# WS2812_MATRIX_3.net
KiCad netlist of a schematic drawn in Altium Designer
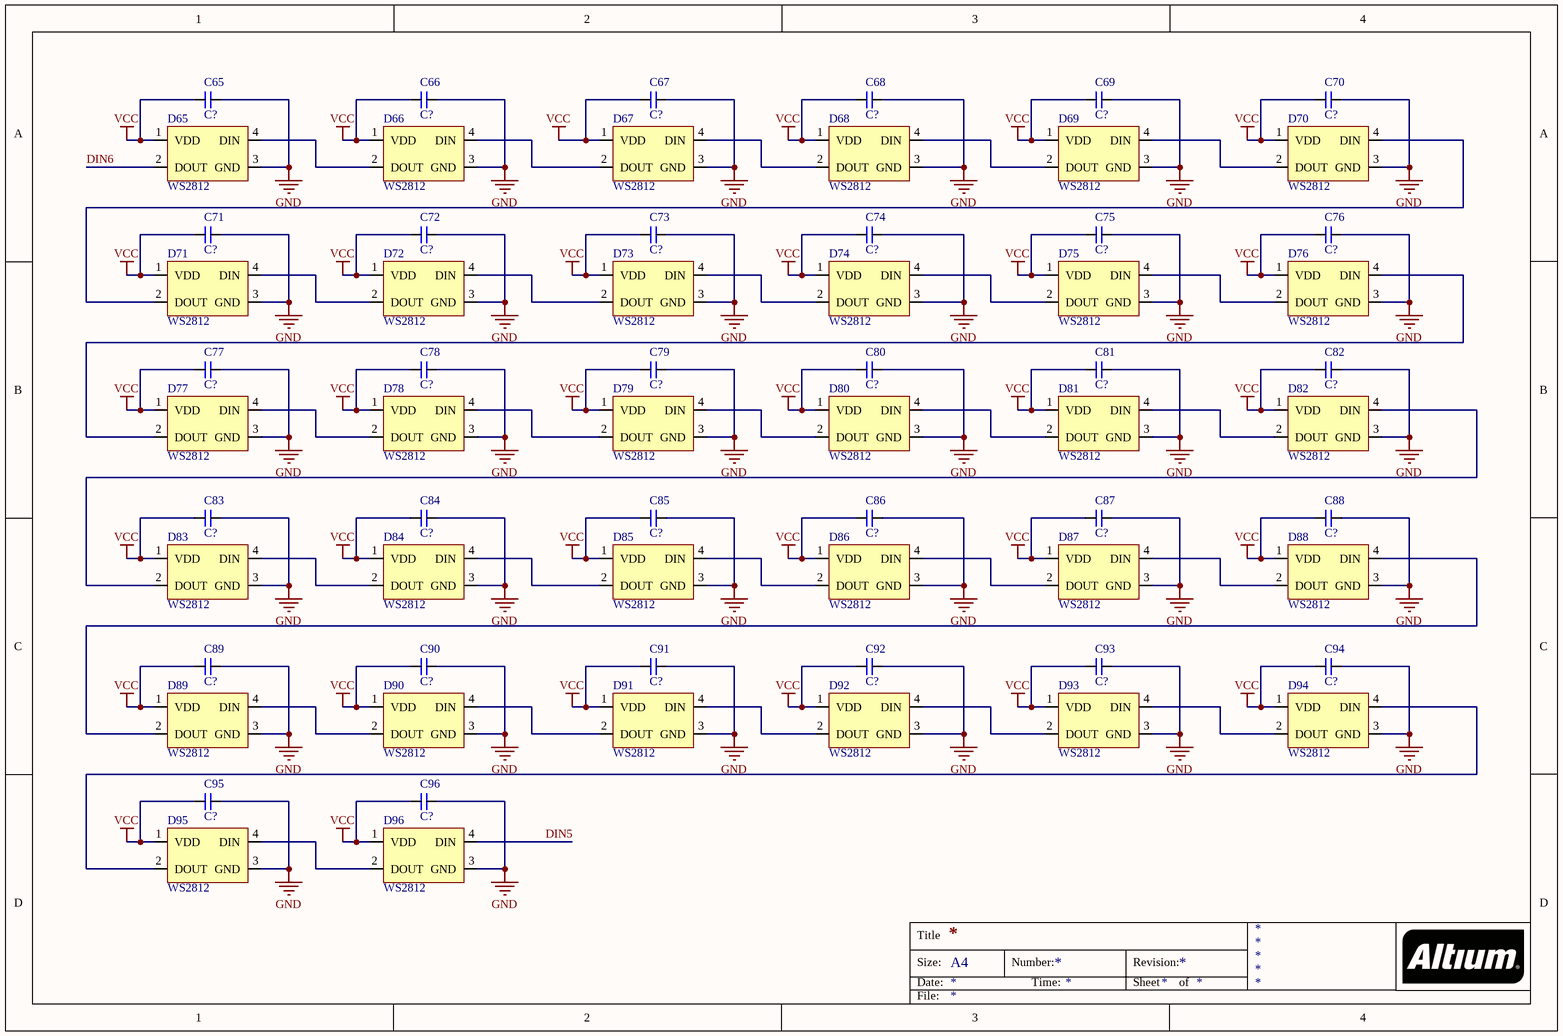
[diagram p0: WS2812_MATRIX_3.SchDoc]

(export (version "E")
  (design (tool "Eeschema 10.0.6"))
  (components
    (comp (ref "C65")
      (value "C?")
      (footprint "C0603")
      (description "Cap")
      (libsource (lib "SCH_Bacsic") (part "CAP"))
    )
    (comp (ref "C66")
      (value "C?")
      (footprint "C0603")
      (description "Cap")
      (libsource (lib "SCH_Bacsic") (part "CAP"))
    )
    (comp (ref "C67")
      (value "C?")
      (footprint "C0603")
      (description "Cap")
      (libsource (lib "SCH_Bacsic") (part "CAP"))
    )
    (comp (ref "C68")
      (value "C?")
      (footprint "C0603")
      (description "Cap")
      (libsource (lib "SCH_Bacsic") (part "CAP"))
    )
    (comp (ref "C69")
      (value "C?")
      (footprint "C0603")
      (description "Cap")
      (libsource (lib "SCH_Bacsic") (part "CAP"))
    )
    (comp (ref "C70")
      (value "C?")
      (footprint "C0603")
      (description "Cap")
      (libsource (lib "SCH_Bacsic") (part "CAP"))
    )
    (comp (ref "C71")
      (value "C?")
      (footprint "C0603")
      (description "Cap")
      (libsource (lib "SCH_Bacsic") (part "CAP"))
    )
    (comp (ref "C72")
      (value "C?")
      (footprint "C0603")
      (description "Cap")
      (libsource (lib "SCH_Bacsic") (part "CAP"))
    )
    (comp (ref "C73")
      (value "C?")
      (footprint "C0603")
      (description "Cap")
      (libsource (lib "SCH_Bacsic") (part "CAP"))
    )
    (comp (ref "C74")
      (value "C?")
      (footprint "C0603")
      (description "Cap")
      (libsource (lib "SCH_Bacsic") (part "CAP"))
    )
    (comp (ref "C75")
      (value "C?")
      (footprint "C0603")
      (description "Cap")
      (libsource (lib "SCH_Bacsic") (part "CAP"))
    )
    (comp (ref "C76")
      (value "C?")
      (footprint "C0603")
      (description "Cap")
      (libsource (lib "SCH_Bacsic") (part "CAP"))
    )
    (comp (ref "C77")
      (value "C?")
      (footprint "C0603")
      (description "Cap")
      (libsource (lib "SCH_Bacsic") (part "CAP"))
    )
    (comp (ref "C78")
      (value "C?")
      (footprint "C0603")
      (description "Cap")
      (libsource (lib "SCH_Bacsic") (part "CAP"))
    )
    (comp (ref "C79")
      (value "C?")
      (footprint "C0603")
      (description "Cap")
      (libsource (lib "SCH_Bacsic") (part "CAP"))
    )
    (comp (ref "C80")
      (value "C?")
      (footprint "C0603")
      (description "Cap")
      (libsource (lib "SCH_Bacsic") (part "CAP"))
    )
    (comp (ref "C81")
      (value "C?")
      (footprint "C0603")
      (description "Cap")
      (libsource (lib "SCH_Bacsic") (part "CAP"))
    )
    (comp (ref "C82")
      (value "C?")
      (footprint "C0603")
      (description "Cap")
      (libsource (lib "SCH_Bacsic") (part "CAP"))
    )
    (comp (ref "C83")
      (value "C?")
      (footprint "C0603")
      (description "Cap")
      (libsource (lib "SCH_Bacsic") (part "CAP"))
    )
    (comp (ref "C84")
      (value "C?")
      (footprint "C0603")
      (description "Cap")
      (libsource (lib "SCH_Bacsic") (part "CAP"))
    )
    (comp (ref "C85")
      (value "C?")
      (footprint "C0603")
      (description "Cap")
      (libsource (lib "SCH_Bacsic") (part "CAP"))
    )
    (comp (ref "C86")
      (value "C?")
      (footprint "C0603")
      (description "Cap")
      (libsource (lib "SCH_Bacsic") (part "CAP"))
    )
    (comp (ref "C87")
      (value "C?")
      (footprint "C0603")
      (description "Cap")
      (libsource (lib "SCH_Bacsic") (part "CAP"))
    )
    (comp (ref "C88")
      (value "C?")
      (footprint "C0603")
      (description "Cap")
      (libsource (lib "SCH_Bacsic") (part "CAP"))
    )
    (comp (ref "C89")
      (value "C?")
      (footprint "C0603")
      (description "Cap")
      (libsource (lib "SCH_Bacsic") (part "CAP"))
    )
    (comp (ref "C90")
      (value "C?")
      (footprint "C0603")
      (description "Cap")
      (libsource (lib "SCH_Bacsic") (part "CAP"))
    )
    (comp (ref "C91")
      (value "C?")
      (footprint "C0603")
      (description "Cap")
      (libsource (lib "SCH_Bacsic") (part "CAP"))
    )
    (comp (ref "C92")
      (value "C?")
      (footprint "C0603")
      (description "Cap")
      (libsource (lib "SCH_Bacsic") (part "CAP"))
    )
    (comp (ref "C93")
      (value "C?")
      (footprint "C0603")
      (description "Cap")
      (libsource (lib "SCH_Bacsic") (part "CAP"))
    )
    (comp (ref "C94")
      (value "C?")
      (footprint "C0603")
      (description "Cap")
      (libsource (lib "SCH_Bacsic") (part "CAP"))
    )
    (comp (ref "C95")
      (value "C?")
      (footprint "C0603")
      (description "Cap")
      (libsource (lib "SCH_Bacsic") (part "CAP"))
    )
    (comp (ref "C96")
      (value "C?")
      (footprint "C0603")
      (description "Cap")
      (libsource (lib "SCH_Bacsic") (part "CAP"))
    )
    (comp (ref "D65")
      (value "WS2812")
      (footprint "WS2812_3528")
      (libsource (lib "SCH_Bacsic") (part "WS2812"))
    )
    (comp (ref "D66")
      (value "WS2812")
      (footprint "WS2812_3528")
      (libsource (lib "SCH_Bacsic") (part "WS2812"))
    )
    (comp (ref "D67")
      (value "WS2812")
      (footprint "WS2812_3528")
      (libsource (lib "SCH_Bacsic") (part "WS2812"))
    )
    (comp (ref "D68")
      (value "WS2812")
      (footprint "WS2812_3528")
      (libsource (lib "SCH_Bacsic") (part "WS2812"))
    )
    (comp (ref "D69")
      (value "WS2812")
      (footprint "WS2812_3528")
      (libsource (lib "SCH_Bacsic") (part "WS2812"))
    )
    (comp (ref "D70")
      (value "WS2812")
      (footprint "WS2812_3528")
      (libsource (lib "SCH_Bacsic") (part "WS2812"))
    )
    (comp (ref "D71")
      (value "WS2812")
      (footprint "WS2812_3528")
      (libsource (lib "SCH_Bacsic") (part "WS2812"))
    )
    (comp (ref "D72")
      (value "WS2812")
      (footprint "WS2812_3528")
      (libsource (lib "SCH_Bacsic") (part "WS2812"))
    )
    (comp (ref "D73")
      (value "WS2812")
      (footprint "WS2812_3528")
      (libsource (lib "SCH_Bacsic") (part "WS2812"))
    )
    (comp (ref "D74")
      (value "WS2812")
      (footprint "WS2812_3528")
      (libsource (lib "SCH_Bacsic") (part "WS2812"))
    )
    (comp (ref "D75")
      (value "WS2812")
      (footprint "WS2812_3528")
      (libsource (lib "SCH_Bacsic") (part "WS2812"))
    )
    (comp (ref "D76")
      (value "WS2812")
      (footprint "WS2812_3528")
      (libsource (lib "SCH_Bacsic") (part "WS2812"))
    )
    (comp (ref "D77")
      (value "WS2812")
      (footprint "WS2812_3528")
      (libsource (lib "SCH_Bacsic") (part "WS2812"))
    )
    (comp (ref "D78")
      (value "WS2812")
      (footprint "WS2812_3528")
      (libsource (lib "SCH_Bacsic") (part "WS2812"))
    )
    (comp (ref "D79")
      (value "WS2812")
      (footprint "WS2812_3528")
      (libsource (lib "SCH_Bacsic") (part "WS2812"))
    )
    (comp (ref "D80")
      (value "WS2812")
      (footprint "WS2812_3528")
      (libsource (lib "SCH_Bacsic") (part "WS2812"))
    )
    (comp (ref "D81")
      (value "WS2812")
      (footprint "WS2812_3528")
      (libsource (lib "SCH_Bacsic") (part "WS2812"))
    )
    (comp (ref "D82")
      (value "WS2812")
      (footprint "WS2812_3528")
      (libsource (lib "SCH_Bacsic") (part "WS2812"))
    )
    (comp (ref "D83")
      (value "WS2812")
      (footprint "WS2812_3528")
      (libsource (lib "SCH_Bacsic") (part "WS2812"))
    )
    (comp (ref "D84")
      (value "WS2812")
      (footprint "WS2812_3528")
      (libsource (lib "SCH_Bacsic") (part "WS2812"))
    )
    (comp (ref "D85")
      (value "WS2812")
      (footprint "WS2812_3528")
      (libsource (lib "SCH_Bacsic") (part "WS2812"))
    )
    (comp (ref "D86")
      (value "WS2812")
      (footprint "WS2812_3528")
      (libsource (lib "SCH_Bacsic") (part "WS2812"))
    )
    (comp (ref "D87")
      (value "WS2812")
      (footprint "WS2812_3528")
      (libsource (lib "SCH_Bacsic") (part "WS2812"))
    )
    (comp (ref "D88")
      (value "WS2812")
      (footprint "WS2812_3528")
      (libsource (lib "SCH_Bacsic") (part "WS2812"))
    )
    (comp (ref "D89")
      (value "WS2812")
      (footprint "WS2812_3528")
      (libsource (lib "SCH_Bacsic") (part "WS2812"))
    )
    (comp (ref "D90")
      (value "WS2812")
      (footprint "WS2812_3528")
      (libsource (lib "SCH_Bacsic") (part "WS2812"))
    )
    (comp (ref "D91")
      (value "WS2812")
      (footprint "WS2812_3528")
      (libsource (lib "SCH_Bacsic") (part "WS2812"))
    )
    (comp (ref "D92")
      (value "WS2812")
      (footprint "WS2812_3528")
      (libsource (lib "SCH_Bacsic") (part "WS2812"))
    )
    (comp (ref "D93")
      (value "WS2812")
      (footprint "WS2812_3528")
      (libsource (lib "SCH_Bacsic") (part "WS2812"))
    )
    (comp (ref "D94")
      (value "WS2812")
      (footprint "WS2812_3528")
      (libsource (lib "SCH_Bacsic") (part "WS2812"))
    )
    (comp (ref "D95")
      (value "WS2812")
      (footprint "WS2812_3528")
      (libsource (lib "SCH_Bacsic") (part "WS2812"))
    )
    (comp (ref "D96")
      (value "WS2812")
      (footprint "WS2812_3528")
      (libsource (lib "SCH_Bacsic") (part "WS2812"))
    )
  )
  (nets
    (net (code "1") (name "/DIN5") (class "Default")
      (node (ref "D96") (pin "4") (pinfunction "DIN_4") (pintype "passive"))
    )
    (net (code "2") (name "/DIN6") (class "Default")
      (node (ref "D65") (pin "2") (pinfunction "DOUT_2") (pintype "passive"))
    )
    (net (code "3") (name "GND") (class "Default")
      (node (ref "C65") (pin "2") (pintype "passive"))
      (node (ref "C66") (pin "2") (pintype "passive"))
      (node (ref "C67") (pin "2") (pintype "passive"))
      (node (ref "C68") (pin "2") (pintype "passive"))
      (node (ref "C69") (pin "2") (pintype "passive"))
      (node (ref "C70") (pin "2") (pintype "passive"))
      (node (ref "C71") (pin "2") (pintype "passive"))
      (node (ref "C72") (pin "2") (pintype "passive"))
      (node (ref "C73") (pin "2") (pintype "passive"))
      (node (ref "C74") (pin "2") (pintype "passive"))
      (node (ref "C75") (pin "2") (pintype "passive"))
      (node (ref "C76") (pin "2") (pintype "passive"))
      (node (ref "C77") (pin "2") (pintype "passive"))
      (node (ref "C78") (pin "2") (pintype "passive"))
      (node (ref "C79") (pin "2") (pintype "passive"))
      (node (ref "C80") (pin "2") (pintype "passive"))
      (node (ref "C81") (pin "2") (pintype "passive"))
      (node (ref "C82") (pin "2") (pintype "passive"))
      (node (ref "C83") (pin "2") (pintype "passive"))
      (node (ref "C84") (pin "2") (pintype "passive"))
      (node (ref "C85") (pin "2") (pintype "passive"))
      (node (ref "C86") (pin "2") (pintype "passive"))
      (node (ref "C87") (pin "2") (pintype "passive"))
      (node (ref "C88") (pin "2") (pintype "passive"))
      (node (ref "C89") (pin "2") (pintype "passive"))
      (node (ref "C90") (pin "2") (pintype "passive"))
      (node (ref "C91") (pin "2") (pintype "passive"))
      (node (ref "C92") (pin "2") (pintype "passive"))
      (node (ref "C93") (pin "2") (pintype "passive"))
      (node (ref "C94") (pin "2") (pintype "passive"))
      (node (ref "C95") (pin "2") (pintype "passive"))
      (node (ref "C96") (pin "2") (pintype "passive"))
      (node (ref "D65") (pin "3") (pinfunction "GND_3") (pintype "passive"))
      (node (ref "D66") (pin "3") (pinfunction "GND_3") (pintype "passive"))
      (node (ref "D67") (pin "3") (pinfunction "GND_3") (pintype "passive"))
      (node (ref "D68") (pin "3") (pinfunction "GND_3") (pintype "passive"))
      (node (ref "D69") (pin "3") (pinfunction "GND_3") (pintype "passive"))
      (node (ref "D70") (pin "3") (pinfunction "GND_3") (pintype "passive"))
      (node (ref "D71") (pin "3") (pinfunction "GND_3") (pintype "passive"))
      (node (ref "D72") (pin "3") (pinfunction "GND_3") (pintype "passive"))
      (node (ref "D73") (pin "3") (pinfunction "GND_3") (pintype "passive"))
      (node (ref "D74") (pin "3") (pinfunction "GND_3") (pintype "passive"))
      (node (ref "D75") (pin "3") (pinfunction "GND_3") (pintype "passive"))
      (node (ref "D76") (pin "3") (pinfunction "GND_3") (pintype "passive"))
      (node (ref "D77") (pin "3") (pinfunction "GND_3") (pintype "passive"))
      (node (ref "D78") (pin "3") (pinfunction "GND_3") (pintype "passive"))
      (node (ref "D79") (pin "3") (pinfunction "GND_3") (pintype "passive"))
      (node (ref "D80") (pin "3") (pinfunction "GND_3") (pintype "passive"))
      (node (ref "D81") (pin "3") (pinfunction "GND_3") (pintype "passive"))
      (node (ref "D82") (pin "3") (pinfunction "GND_3") (pintype "passive"))
      (node (ref "D83") (pin "3") (pinfunction "GND_3") (pintype "passive"))
      (node (ref "D84") (pin "3") (pinfunction "GND_3") (pintype "passive"))
      (node (ref "D85") (pin "3") (pinfunction "GND_3") (pintype "passive"))
      (node (ref "D86") (pin "3") (pinfunction "GND_3") (pintype "passive"))
      (node (ref "D87") (pin "3") (pinfunction "GND_3") (pintype "passive"))
      (node (ref "D88") (pin "3") (pinfunction "GND_3") (pintype "passive"))
      (node (ref "D89") (pin "3") (pinfunction "GND_3") (pintype "passive"))
      (node (ref "D90") (pin "3") (pinfunction "GND_3") (pintype "passive"))
      (node (ref "D91") (pin "3") (pinfunction "GND_3") (pintype "passive"))
      (node (ref "D92") (pin "3") (pinfunction "GND_3") (pintype "passive"))
      (node (ref "D93") (pin "3") (pinfunction "GND_3") (pintype "passive"))
      (node (ref "D94") (pin "3") (pinfunction "GND_3") (pintype "passive"))
      (node (ref "D95") (pin "3") (pinfunction "GND_3") (pintype "passive"))
      (node (ref "D96") (pin "3") (pinfunction "GND_3") (pintype "passive"))
    )
    (net (code "4") (name "Net-(D65-DIN)") (class "Default")
      (node (ref "D65") (pin "4") (pinfunction "DIN_4") (pintype "passive"))
      (node (ref "D66") (pin "2") (pinfunction "DOUT_2") (pintype "passive"))
    )
    (net (code "5") (name "Net-(D66-DIN)") (class "Default")
      (node (ref "D66") (pin "4") (pinfunction "DIN_4") (pintype "passive"))
      (node (ref "D67") (pin "2") (pinfunction "DOUT_2") (pintype "passive"))
    )
    (net (code "6") (name "Net-(D67-DIN)") (class "Default")
      (node (ref "D67") (pin "4") (pinfunction "DIN_4") (pintype "passive"))
      (node (ref "D68") (pin "2") (pinfunction "DOUT_2") (pintype "passive"))
    )
    (net (code "7") (name "Net-(D68-DIN)") (class "Default")
      (node (ref "D68") (pin "4") (pinfunction "DIN_4") (pintype "passive"))
      (node (ref "D69") (pin "2") (pinfunction "DOUT_2") (pintype "passive"))
    )
    (net (code "8") (name "Net-(D69-DIN)") (class "Default")
      (node (ref "D69") (pin "4") (pinfunction "DIN_4") (pintype "passive"))
      (node (ref "D70") (pin "2") (pinfunction "DOUT_2") (pintype "passive"))
    )
    (net (code "9") (name "Net-(D70-DIN)") (class "Default")
      (node (ref "D70") (pin "4") (pinfunction "DIN_4") (pintype "passive"))
      (node (ref "D71") (pin "2") (pinfunction "DOUT_2") (pintype "passive"))
    )
    (net (code "10") (name "Net-(D71-DIN)") (class "Default")
      (node (ref "D71") (pin "4") (pinfunction "DIN_4") (pintype "passive"))
      (node (ref "D72") (pin "2") (pinfunction "DOUT_2") (pintype "passive"))
    )
    (net (code "11") (name "Net-(D72-DIN)") (class "Default")
      (node (ref "D72") (pin "4") (pinfunction "DIN_4") (pintype "passive"))
      (node (ref "D73") (pin "2") (pinfunction "DOUT_2") (pintype "passive"))
    )
    (net (code "12") (name "Net-(D73-DIN)") (class "Default")
      (node (ref "D73") (pin "4") (pinfunction "DIN_4") (pintype "passive"))
      (node (ref "D74") (pin "2") (pinfunction "DOUT_2") (pintype "passive"))
    )
    (net (code "13") (name "Net-(D74-DIN)") (class "Default")
      (node (ref "D74") (pin "4") (pinfunction "DIN_4") (pintype "passive"))
      (node (ref "D75") (pin "2") (pinfunction "DOUT_2") (pintype "passive"))
    )
    (net (code "14") (name "Net-(D75-DIN)") (class "Default")
      (node (ref "D75") (pin "4") (pinfunction "DIN_4") (pintype "passive"))
      (node (ref "D76") (pin "2") (pinfunction "DOUT_2") (pintype "passive"))
    )
    (net (code "15") (name "Net-(D76-DIN)") (class "Default")
      (node (ref "D76") (pin "4") (pinfunction "DIN_4") (pintype "passive"))
      (node (ref "D77") (pin "2") (pinfunction "DOUT_2") (pintype "passive"))
    )
    (net (code "16") (name "Net-(D77-DIN)") (class "Default")
      (node (ref "D77") (pin "4") (pinfunction "DIN_4") (pintype "passive"))
      (node (ref "D78") (pin "2") (pinfunction "DOUT_2") (pintype "passive"))
    )
    (net (code "17") (name "Net-(D78-DIN)") (class "Default")
      (node (ref "D78") (pin "4") (pinfunction "DIN_4") (pintype "passive"))
      (node (ref "D79") (pin "2") (pinfunction "DOUT_2") (pintype "passive"))
    )
    (net (code "18") (name "Net-(D79-DIN)") (class "Default")
      (node (ref "D79") (pin "4") (pinfunction "DIN_4") (pintype "passive"))
      (node (ref "D80") (pin "2") (pinfunction "DOUT_2") (pintype "passive"))
    )
    (net (code "19") (name "Net-(D80-DIN)") (class "Default")
      (node (ref "D80") (pin "4") (pinfunction "DIN_4") (pintype "passive"))
      (node (ref "D81") (pin "2") (pinfunction "DOUT_2") (pintype "passive"))
    )
    (net (code "20") (name "Net-(D81-DIN)") (class "Default")
      (node (ref "D81") (pin "4") (pinfunction "DIN_4") (pintype "passive"))
      (node (ref "D82") (pin "2") (pinfunction "DOUT_2") (pintype "passive"))
    )
    (net (code "21") (name "Net-(D82-DIN)") (class "Default")
      (node (ref "D82") (pin "4") (pinfunction "DIN_4") (pintype "passive"))
      (node (ref "D83") (pin "2") (pinfunction "DOUT_2") (pintype "passive"))
    )
    (net (code "22") (name "Net-(D83-DIN)") (class "Default")
      (node (ref "D83") (pin "4") (pinfunction "DIN_4") (pintype "passive"))
      (node (ref "D84") (pin "2") (pinfunction "DOUT_2") (pintype "passive"))
    )
    (net (code "23") (name "Net-(D84-DIN)") (class "Default")
      (node (ref "D84") (pin "4") (pinfunction "DIN_4") (pintype "passive"))
      (node (ref "D85") (pin "2") (pinfunction "DOUT_2") (pintype "passive"))
    )
    (net (code "24") (name "Net-(D85-DIN)") (class "Default")
      (node (ref "D85") (pin "4") (pinfunction "DIN_4") (pintype "passive"))
      (node (ref "D86") (pin "2") (pinfunction "DOUT_2") (pintype "passive"))
    )
    (net (code "25") (name "Net-(D86-DIN)") (class "Default")
      (node (ref "D86") (pin "4") (pinfunction "DIN_4") (pintype "passive"))
      (node (ref "D87") (pin "2") (pinfunction "DOUT_2") (pintype "passive"))
    )
    (net (code "26") (name "Net-(D87-DIN)") (class "Default")
      (node (ref "D87") (pin "4") (pinfunction "DIN_4") (pintype "passive"))
      (node (ref "D88") (pin "2") (pinfunction "DOUT_2") (pintype "passive"))
    )
    (net (code "27") (name "Net-(D88-DIN)") (class "Default")
      (node (ref "D88") (pin "4") (pinfunction "DIN_4") (pintype "passive"))
      (node (ref "D89") (pin "2") (pinfunction "DOUT_2") (pintype "passive"))
    )
    (net (code "28") (name "Net-(D89-DIN)") (class "Default")
      (node (ref "D89") (pin "4") (pinfunction "DIN_4") (pintype "passive"))
      (node (ref "D90") (pin "2") (pinfunction "DOUT_2") (pintype "passive"))
    )
    (net (code "29") (name "Net-(D90-DIN)") (class "Default")
      (node (ref "D90") (pin "4") (pinfunction "DIN_4") (pintype "passive"))
      (node (ref "D91") (pin "2") (pinfunction "DOUT_2") (pintype "passive"))
    )
    (net (code "30") (name "Net-(D91-DIN)") (class "Default")
      (node (ref "D91") (pin "4") (pinfunction "DIN_4") (pintype "passive"))
      (node (ref "D92") (pin "2") (pinfunction "DOUT_2") (pintype "passive"))
    )
    (net (code "31") (name "Net-(D92-DIN)") (class "Default")
      (node (ref "D92") (pin "4") (pinfunction "DIN_4") (pintype "passive"))
      (node (ref "D93") (pin "2") (pinfunction "DOUT_2") (pintype "passive"))
    )
    (net (code "32") (name "Net-(D93-DIN)") (class "Default")
      (node (ref "D93") (pin "4") (pinfunction "DIN_4") (pintype "passive"))
      (node (ref "D94") (pin "2") (pinfunction "DOUT_2") (pintype "passive"))
    )
    (net (code "33") (name "Net-(D94-DIN)") (class "Default")
      (node (ref "D94") (pin "4") (pinfunction "DIN_4") (pintype "passive"))
      (node (ref "D95") (pin "2") (pinfunction "DOUT_2") (pintype "passive"))
    )
    (net (code "34") (name "Net-(D95-DIN)") (class "Default")
      (node (ref "D95") (pin "4") (pinfunction "DIN_4") (pintype "passive"))
      (node (ref "D96") (pin "2") (pinfunction "DOUT_2") (pintype "passive"))
    )
    (net (code "35") (name "VCC") (class "Default")
      (node (ref "C65") (pin "1") (pintype "passive"))
      (node (ref "C66") (pin "1") (pintype "passive"))
      (node (ref "C67") (pin "1") (pintype "passive"))
      (node (ref "C68") (pin "1") (pintype "passive"))
      (node (ref "C69") (pin "1") (pintype "passive"))
      (node (ref "C70") (pin "1") (pintype "passive"))
      (node (ref "C71") (pin "1") (pintype "passive"))
      (node (ref "C72") (pin "1") (pintype "passive"))
      (node (ref "C73") (pin "1") (pintype "passive"))
      (node (ref "C74") (pin "1") (pintype "passive"))
      (node (ref "C75") (pin "1") (pintype "passive"))
      (node (ref "C76") (pin "1") (pintype "passive"))
      (node (ref "C77") (pin "1") (pintype "passive"))
      (node (ref "C78") (pin "1") (pintype "passive"))
      (node (ref "C79") (pin "1") (pintype "passive"))
      (node (ref "C80") (pin "1") (pintype "passive"))
      (node (ref "C81") (pin "1") (pintype "passive"))
      (node (ref "C82") (pin "1") (pintype "passive"))
      (node (ref "C83") (pin "1") (pintype "passive"))
      (node (ref "C84") (pin "1") (pintype "passive"))
      (node (ref "C85") (pin "1") (pintype "passive"))
      (node (ref "C86") (pin "1") (pintype "passive"))
      (node (ref "C87") (pin "1") (pintype "passive"))
      (node (ref "C88") (pin "1") (pintype "passive"))
      (node (ref "C89") (pin "1") (pintype "passive"))
      (node (ref "C90") (pin "1") (pintype "passive"))
      (node (ref "C91") (pin "1") (pintype "passive"))
      (node (ref "C92") (pin "1") (pintype "passive"))
      (node (ref "C93") (pin "1") (pintype "passive"))
      (node (ref "C94") (pin "1") (pintype "passive"))
      (node (ref "C95") (pin "1") (pintype "passive"))
      (node (ref "C96") (pin "1") (pintype "passive"))
      (node (ref "D65") (pin "1") (pinfunction "VDD_1") (pintype "passive"))
      (node (ref "D66") (pin "1") (pinfunction "VDD_1") (pintype "passive"))
      (node (ref "D67") (pin "1") (pinfunction "VDD_1") (pintype "passive"))
      (node (ref "D68") (pin "1") (pinfunction "VDD_1") (pintype "passive"))
      (node (ref "D69") (pin "1") (pinfunction "VDD_1") (pintype "passive"))
      (node (ref "D70") (pin "1") (pinfunction "VDD_1") (pintype "passive"))
      (node (ref "D71") (pin "1") (pinfunction "VDD_1") (pintype "passive"))
      (node (ref "D72") (pin "1") (pinfunction "VDD_1") (pintype "passive"))
      (node (ref "D73") (pin "1") (pinfunction "VDD_1") (pintype "passive"))
      (node (ref "D74") (pin "1") (pinfunction "VDD_1") (pintype "passive"))
      (node (ref "D75") (pin "1") (pinfunction "VDD_1") (pintype "passive"))
      (node (ref "D76") (pin "1") (pinfunction "VDD_1") (pintype "passive"))
      (node (ref "D77") (pin "1") (pinfunction "VDD_1") (pintype "passive"))
      (node (ref "D78") (pin "1") (pinfunction "VDD_1") (pintype "passive"))
      (node (ref "D79") (pin "1") (pinfunction "VDD_1") (pintype "passive"))
      (node (ref "D80") (pin "1") (pinfunction "VDD_1") (pintype "passive"))
      (node (ref "D81") (pin "1") (pinfunction "VDD_1") (pintype "passive"))
      (node (ref "D82") (pin "1") (pinfunction "VDD_1") (pintype "passive"))
      (node (ref "D83") (pin "1") (pinfunction "VDD_1") (pintype "passive"))
      (node (ref "D84") (pin "1") (pinfunction "VDD_1") (pintype "passive"))
      (node (ref "D85") (pin "1") (pinfunction "VDD_1") (pintype "passive"))
      (node (ref "D86") (pin "1") (pinfunction "VDD_1") (pintype "passive"))
      (node (ref "D87") (pin "1") (pinfunction "VDD_1") (pintype "passive"))
      (node (ref "D88") (pin "1") (pinfunction "VDD_1") (pintype "passive"))
      (node (ref "D89") (pin "1") (pinfunction "VDD_1") (pintype "passive"))
      (node (ref "D90") (pin "1") (pinfunction "VDD_1") (pintype "passive"))
      (node (ref "D91") (pin "1") (pinfunction "VDD_1") (pintype "passive"))
      (node (ref "D92") (pin "1") (pinfunction "VDD_1") (pintype "passive"))
      (node (ref "D93") (pin "1") (pinfunction "VDD_1") (pintype "passive"))
      (node (ref "D94") (pin "1") (pinfunction "VDD_1") (pintype "passive"))
      (node (ref "D95") (pin "1") (pinfunction "VDD_1") (pintype "passive"))
      (node (ref "D96") (pin "1") (pinfunction "VDD_1") (pintype "passive"))
    )
  )
)
